# UNI-DIRECTIONAL_HIGH-SIDE_SWITCH_10V.net
KiCad netlist of a schematic drawn in Altium Designer
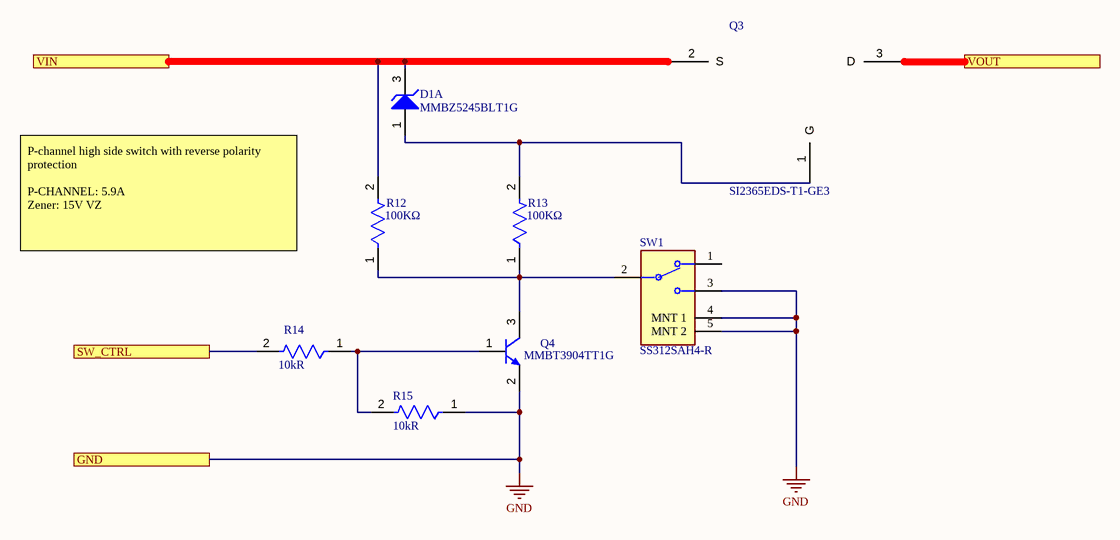
[diagram p0: UNI-DIRECTIONAL HIGH-SIDE SWITCH 10V.SchDoc]

(export (version "E")
  (design (tool "Eeschema 10.0.6"))
  (components
    (comp (ref "D1")
      (value "MMBZ5245BLT1G")
      (footprint "ONSC-SOT-23-3-318-08_V")
      (description "Zener Voltage Regulator, 225 mW, 3-Pin SOT-23, Pb-Free, Tape and Reel")
      (fields (field (name "MANUFACTURER") "On Semiconductor"))
      (libsource (lib "Altium Content Vault") (part "ONSC-A1K3-3"))
    )
    (comp (ref "Q3")
      (value "SI2365EDS-T1-GE3")
      (footprint "SOT95P237X110-3M")
      (fields (field (name "MANUFACTURER") "Vishay Siliconix"))
      (libsource (lib "SI2365EDS-T1-GE3") (part "SI2365EDS-T1-GE3"))
    )
    (comp (ref "Q4")
      (value "MMBT3904TT1G")
      (footprint "ONSC-SC-75-3-463-01_V")
      (description "General Purpose Transistor, NPN Silicon, 3-Pin SC-75, Pb-Free, Tape and Reel")
      (fields (field (name "MANUFACTURER") "On Semiconductor"))
      (libsource (lib "Altium Content Vault") (part "ONSC-NPN-B1E2C3-3"))
    )
    (comp (ref "R12")
      (value "RT0402FRE07100KL")
      (footprint "FP-RT0402-MFG")
      (description "RES 100K OHM 1/16W 1% SMD 0402")
      (fields
        (field (name "MANUFACTURER") "Yageo")
        (field (name "OCTOPART") "https://octopart.com/rt0402fre07100kl-yageo-1444458")
        (field (name "RESISTANCE") "100KΩ")
      )
      (libsource (lib "Altium Content Vault") (part "1029c3af85768c4190bb7ad29bc67b5"))
    )
    (comp (ref "R13")
      (value "RT0402FRE07100KL")
      (footprint "FP-RT0402-MFG")
      (description "RES 100K OHM 1/16W 1% SMD 0402")
      (fields
        (field (name "MANUFACTURER") "Yageo")
        (field (name "OCTOPART") "https://octopart.com/rt0402fre07100kl-yageo-1444458")
        (field (name "RESISTANCE") "100KΩ")
      )
      (libsource (lib "Altium Content Vault") (part "1029c3af85768c4190bb7ad29bc67b5"))
    )
    (comp (ref "R14")
      (value "CRG0402F10K")
      (footprint "FP-CRG0402-IPC_B")
      (description "RES SMD 10K OHM 1% 1/16W 0402")
      (fields (field (name "RESISTANCE") "10kR") (field (name "TOLERANCE") "1%"))
      (libsource (lib "Altium Content Vault") (part "1029c3af85768c4190bb7ad29bc67b5"))
    )
    (comp (ref "R15")
      (value "CRG0402F10K")
      (footprint "FP-CRG0402-IPC_B")
      (description "RES SMD 10K OHM 1% 1/16W 0402")
      (fields (field (name "RESISTANCE") "10kR") (field (name "TOLERANCE") "1%"))
      (libsource (lib "Altium Content Vault") (part "1029c3af85768c4190bb7ad29bc67b5"))
    )
    (comp (ref "SW1")
      (value "SS312SAH4-R")
      (footprint "FP-SS312SAH4-R-MFG")
      (description "SWITCH SLIDE SPDT 0.4VA 28V")
      (libsource (lib "Altium Content Vault") (part "4c976abc4051e389b5557946779e9a3"))
    )
  )
  (nets
    (net (code "1") (name "/SW_CTRL") (class "Default")
      (node (ref "R14") (pin "2") (pinfunction "2_2") (pintype "passive"))
    )
    (net (code "2") (name "/VIN") (class "Default")
      (node (ref "D1") (pin "3") (pinfunction "K_3") (pintype "passive"))
      (node (ref "Q3") (pin "2") (pinfunction "S_2") (pintype "passive"))
      (node (ref "R12") (pin "2") (pinfunction "2_2") (pintype "passive"))
    )
    (net (code "3") (name "/VOUT") (class "Default")
      (node (ref "Q3") (pin "3") (pinfunction "D_3") (pintype "passive"))
    )
    (net (code "4") (name "GND") (class "Default")
      (node (ref "Q4") (pin "2") (pinfunction "E_2") (pintype "passive"))
      (node (ref "R15") (pin "1") (pinfunction "1_1") (pintype "passive"))
      (node (ref "SW1") (pin "3") (pinfunction "3_3") (pintype "passive"))
      (node (ref "SW1") (pin "4") (pinfunction "MNT_1_4") (pintype "passive"))
      (node (ref "SW1") (pin "5") (pinfunction "MNT_2_5") (pintype "passive"))
    )
    (net (code "5") (name "Net-(D1A-A)") (class "Default")
      (node (ref "D1") (pin "1") (pinfunction "A_1") (pintype "passive"))
      (node (ref "Q3") (pin "1") (pinfunction "G_1") (pintype "passive"))
      (node (ref "R13") (pin "2") (pinfunction "2_2") (pintype "passive"))
    )
    (net (code "6") (name "Net-(Q4-B)") (class "Default")
      (node (ref "Q4") (pin "1") (pinfunction "B_1") (pintype "passive"))
      (node (ref "R14") (pin "1") (pinfunction "1_1") (pintype "passive"))
      (node (ref "R15") (pin "2") (pinfunction "2_2") (pintype "passive"))
    )
    (net (code "7") (name "Net-(Q4-C)") (class "Default")
      (node (ref "Q4") (pin "3") (pinfunction "C_3") (pintype "passive"))
      (node (ref "R12") (pin "1") (pinfunction "1_1") (pintype "passive"))
      (node (ref "R13") (pin "1") (pinfunction "1_1") (pintype "passive"))
      (node (ref "SW1") (pin "2") (pinfunction "COM_2") (pintype "passive"))
    )
    (net (code "8") (name "unconnected-(SW1-Pad1)") (class "Default")
      (node (ref "SW1") (pin "1") (pinfunction "1_1") (pintype "passive"))
    )
  )
)
